# EEPROM.net
KiCad netlist of a schematic drawn in Altium Designer
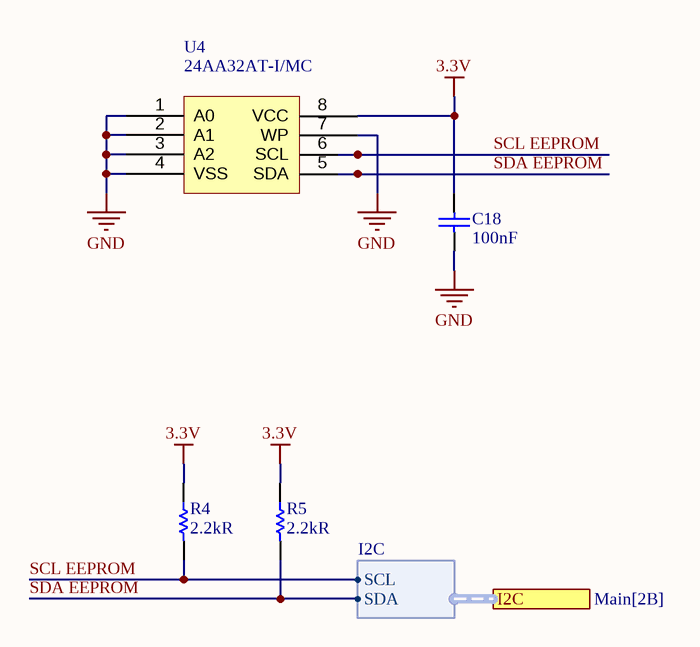
[diagram p0: EEPROM.SchDoc]

(export (version "E")
  (design (tool "Eeschema 10.0.6"))
  (components
    (comp (ref "C18")
      (value "100nF")
      (footprint "Capacitor 0402")
      (libsource (lib "x-io") (part "Capacitor"))
    )
    (comp (ref "R4") (value "2.2kR") (footprint "Resistor 0402") (libsource (lib "x-io") (part "Resistor")))
    (comp (ref "R5") (value "2.2kR") (footprint "Resistor 0402") (libsource (lib "x-io") (part "Resistor")))
    (comp (ref "U4")
      (value "24AA32AT-I/MC")
      (footprint "TDFN-8 2x3mm")
      (libsource (lib "x-io") (part "24AA32A"))
    )
  )
  (nets
    (net (code "2") (name "/SCL EEPROM") (class "Default")
      (node (ref "R4") (pin "1") (pinfunction "1_1") (pintype "passive"))
      (node (ref "U4") (pin "6") (pinfunction "SCL_6") (pintype "passive"))
    )
    (net (code "3") (name "/SDA EEPROM") (class "Default")
      (node (ref "R5") (pin "1") (pinfunction "1_1") (pintype "passive"))
      (node (ref "U4") (pin "5") (pinfunction "SDA_5") (pintype "passive"))
    )
    (net (code "5") (name "3.3V") (class "Default")
      (node (ref "C18") (pin "2") (pinfunction "2_2") (pintype "passive"))
      (node (ref "R4") (pin "2") (pinfunction "2_2") (pintype "passive"))
      (node (ref "R5") (pin "2") (pinfunction "2_2") (pintype "passive"))
      (node (ref "U4") (pin "8") (pinfunction "VCC_8") (pintype "passive"))
    )
    (net (code "6") (name "GND") (class "Default")
      (node (ref "C18") (pin "1") (pinfunction "1_1") (pintype "passive"))
      (node (ref "U4") (pin "1") (pinfunction "A0_1") (pintype "passive"))
      (node (ref "U4") (pin "2") (pinfunction "A1_2") (pintype "passive"))
      (node (ref "U4") (pin "3") (pinfunction "A2_3") (pintype "passive"))
      (node (ref "U4") (pin "4") (pinfunction "VSS_4") (pintype "passive"))
      (node (ref "U4") (pin "7") (pinfunction "WP_7") (pintype "passive"))
    )
  )
)
